# RP2040LED.net
KiCad netlist of a schematic drawn in Altium Designer
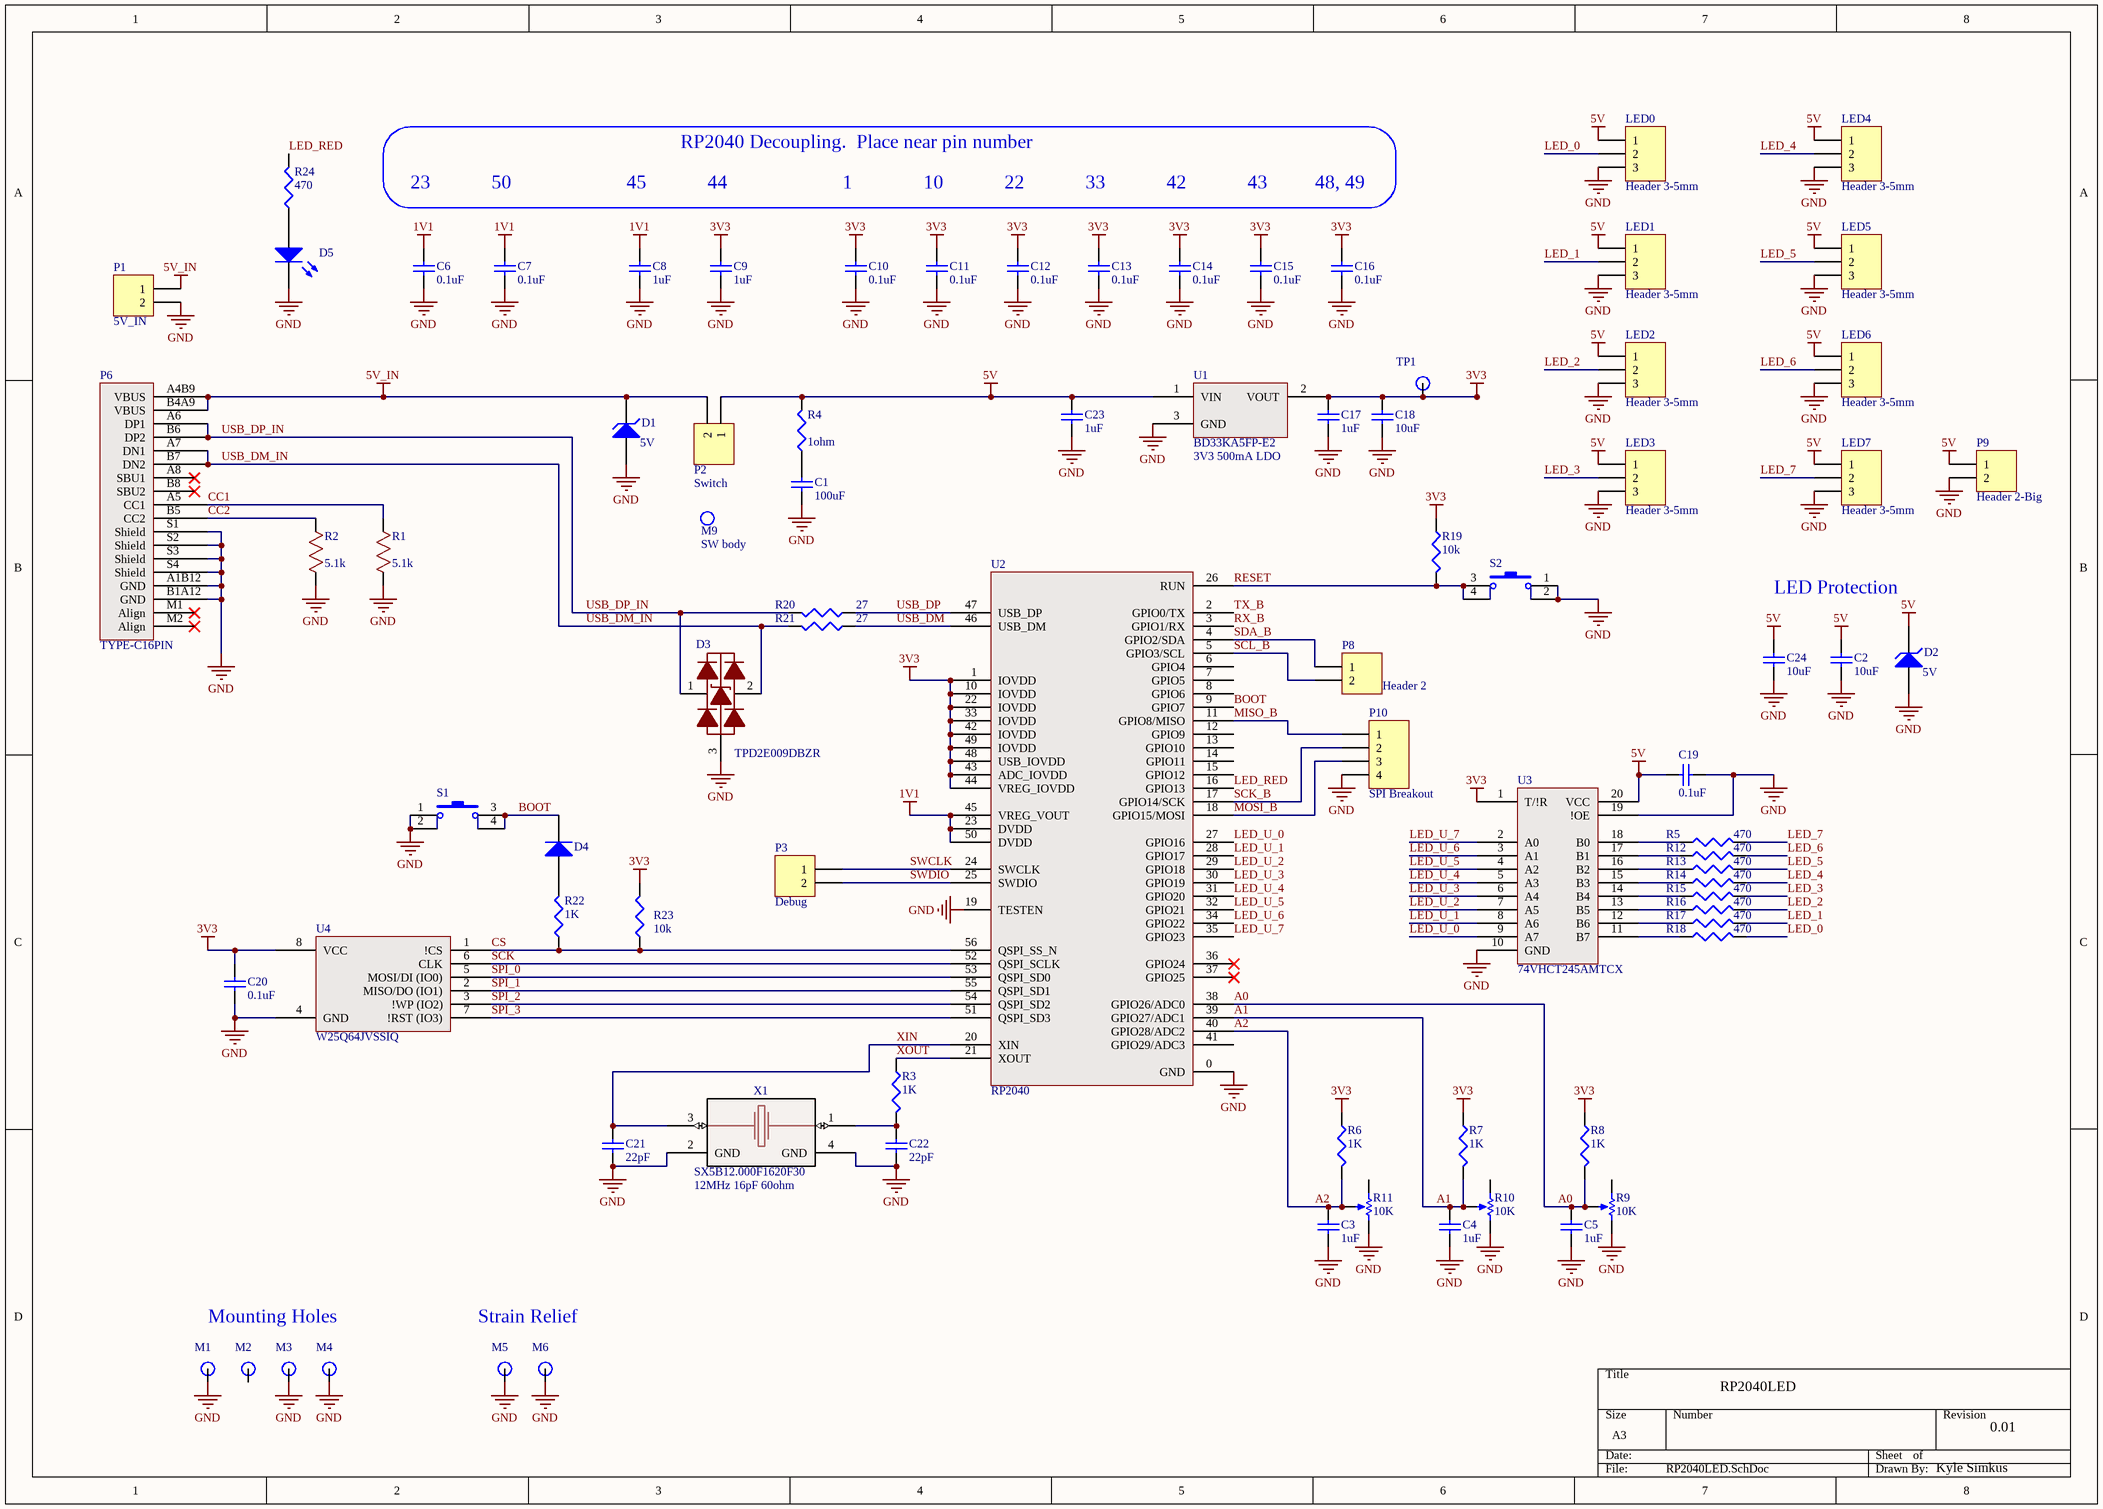
[diagram p0: RP2040LED.SchDoc]

(export (version "E")
  (design (tool "Eeschema 10.0.6"))
  (components
    (comp (ref "C1")
      (value "100uF")
      (footprint "1210 [3225] - C")
      (description "10V 100uF X5R ±20% 1210  Multilayer Ceramic Capacitors MLCC - SMD/SMT ROHS")
      (fields (field (name "VOLTAGE") "10V") (field (name "Comment") "CAP"))
      (libsource (lib "Miscellaneous Devices") (part "Cap Semi"))
    )
    (comp (ref "C2")
      (value "10uF")
      (footprint "0805 [2012] - C")
      (description "MULTILAYER CERAMIC CAPACITORS MLCC - SMD/SMT 10UF 25V 0805 ROHS")
      (fields (field (name "VOLTAGE") "V") (field (name "MPN") "CL21A106KOQNNNE"))
      (libsource (lib "Miscellaneous Devices") (part "Cap Semi"))
    )
    (comp (ref "C3")
      (value "1uF")
      (footprint "0603C")
      (description "MULTILAYER CERAMIC CAPACITORS MLCC - SMD/SMT 1UF 50V 0603 ROHS")
      (fields (field (name "VOLTAGE") "V") (field (name "MPN") "CL10A105KA8NNNC"))
      (libsource (lib "Miscellaneous Devices") (part "Cap Semi"))
    )
    (comp (ref "C4")
      (value "1uF")
      (footprint "0603C")
      (description "MULTILAYER CERAMIC CAPACITORS MLCC - SMD/SMT 1UF 50V 0603 ROHS")
      (fields (field (name "VOLTAGE") "V") (field (name "MPN") "CL10A105KA8NNNC"))
      (libsource (lib "Miscellaneous Devices") (part "Cap Semi"))
    )
    (comp (ref "C5")
      (value "1uF")
      (footprint "0603C")
      (description "MULTILAYER CERAMIC CAPACITORS MLCC - SMD/SMT 1UF 50V 0603 ROHS")
      (fields (field (name "VOLTAGE") "V") (field (name "MPN") "CL10A105KA8NNNC"))
      (libsource (lib "Miscellaneous Devices") (part "Cap Semi"))
    )
    (comp (ref "C6")
      (value "0.1uF")
      (footprint "0402C")
      (description "MULTILAYER CERAMIC CAPACITORS MLCC - SMD/SMT 100NF 50V 0603 ROHS")
      (fields (field (name "VOLTAGE") "V") (field (name "MPN") "CL05B104KB54PNC"))
      (libsource (lib "Miscellaneous Devices") (part "Cap Semi"))
    )
    (comp (ref "C7")
      (value "0.1uF")
      (footprint "0402C")
      (description "MULTILAYER CERAMIC CAPACITORS MLCC - SMD/SMT 100NF 50V 0603 ROHS")
      (fields (field (name "VOLTAGE") "V") (field (name "MPN") "CL05B104KB54PNC"))
      (libsource (lib "Miscellaneous Devices") (part "Cap Semi"))
    )
    (comp (ref "C8")
      (value "1uF")
      (footprint "0603C")
      (description "MULTILAYER CERAMIC CAPACITORS MLCC - SMD/SMT 1UF 50V 0603 ROHS")
      (fields (field (name "VOLTAGE") "V") (field (name "MPN") "CL10A105KA8NNNC"))
      (libsource (lib "Miscellaneous Devices") (part "Cap Semi"))
    )
    (comp (ref "C9")
      (value "1uF")
      (footprint "0603C")
      (description "MULTILAYER CERAMIC CAPACITORS MLCC - SMD/SMT 1UF 50V 0603 ROHS")
      (fields (field (name "VOLTAGE") "V") (field (name "MPN") "CL10A105KA8NNNC"))
      (libsource (lib "Miscellaneous Devices") (part "Cap Semi"))
    )
    (comp (ref "C10")
      (value "0.1uF")
      (footprint "0402C")
      (description "MULTILAYER CERAMIC CAPACITORS MLCC - SMD/SMT 100NF 50V 0603 ROHS")
      (fields (field (name "VOLTAGE") "V") (field (name "MPN") "CL05B104KB54PNC"))
      (libsource (lib "Miscellaneous Devices") (part "Cap Semi"))
    )
    (comp (ref "C11")
      (value "0.1uF")
      (footprint "0402C")
      (description "MULTILAYER CERAMIC CAPACITORS MLCC - SMD/SMT 100NF 50V 0603 ROHS")
      (fields (field (name "VOLTAGE") "V") (field (name "MPN") "CL05B104KB54PNC"))
      (libsource (lib "Miscellaneous Devices") (part "Cap Semi"))
    )
    (comp (ref "C12")
      (value "0.1uF")
      (footprint "0402C")
      (description "MULTILAYER CERAMIC CAPACITORS MLCC - SMD/SMT 100NF 50V 0603 ROHS")
      (fields (field (name "VOLTAGE") "V") (field (name "MPN") "CL05B104KB54PNC"))
      (libsource (lib "Miscellaneous Devices") (part "Cap Semi"))
    )
    (comp (ref "C13")
      (value "0.1uF")
      (footprint "0402C")
      (description "MULTILAYER CERAMIC CAPACITORS MLCC - SMD/SMT 100NF 50V 0603 ROHS")
      (fields (field (name "VOLTAGE") "V") (field (name "MPN") "CL05B104KB54PNC"))
      (libsource (lib "Miscellaneous Devices") (part "Cap Semi"))
    )
    (comp (ref "C14")
      (value "0.1uF")
      (footprint "0402C")
      (description "MULTILAYER CERAMIC CAPACITORS MLCC - SMD/SMT 100NF 50V 0603 ROHS")
      (fields (field (name "VOLTAGE") "V") (field (name "MPN") "CL05B104KB54PNC"))
      (libsource (lib "Miscellaneous Devices") (part "Cap Semi"))
    )
    (comp (ref "C15")
      (value "0.1uF")
      (footprint "0402C")
      (description "MULTILAYER CERAMIC CAPACITORS MLCC - SMD/SMT 100NF 50V 0603 ROHS")
      (fields (field (name "VOLTAGE") "V") (field (name "MPN") "CL05B104KB54PNC"))
      (libsource (lib "Miscellaneous Devices") (part "Cap Semi"))
    )
    (comp (ref "C16")
      (value "0.1uF")
      (footprint "0402C")
      (description "MULTILAYER CERAMIC CAPACITORS MLCC - SMD/SMT 100NF 50V 0603 ROHS")
      (fields (field (name "VOLTAGE") "V") (field (name "MPN") "CL05B104KB54PNC"))
      (libsource (lib "Miscellaneous Devices") (part "Cap Semi"))
    )
    (comp (ref "C17")
      (value "1uF")
      (footprint "0603C")
      (description "MULTILAYER CERAMIC CAPACITORS MLCC - SMD/SMT 1UF 50V 0603 ROHS")
      (fields (field (name "VOLTAGE") "V") (field (name "MPN") "CL10A105KA8NNNC"))
      (libsource (lib "Miscellaneous Devices") (part "Cap Semi"))
    )
    (comp (ref "C18")
      (value "10uF")
      (footprint "0805 [2012] - C")
      (description "MULTILAYER CERAMIC CAPACITORS MLCC - SMD/SMT 10UF 25V 0805 ROHS")
      (fields (field (name "VOLTAGE") "V") (field (name "MPN") "CL21A106KOQNNNE"))
      (libsource (lib "Miscellaneous Devices") (part "Cap Semi"))
    )
    (comp (ref "C19")
      (value "0.1uF")
      (footprint "0603C")
      (description "MULTILAYER CERAMIC CAPACITORS MLCC - SMD/SMT 100NF 50V 0603 ROHS")
      (fields (field (name "VOLTAGE") "V") (field (name "MPN") "CL10B104KB8NNNC"))
      (libsource (lib "Miscellaneous Devices") (part "Cap Semi"))
    )
    (comp (ref "C20")
      (value "0.1uF")
      (footprint "0603C")
      (description "MULTILAYER CERAMIC CAPACITORS MLCC - SMD/SMT 100NF 50V 0603 ROHS")
      (fields (field (name "VOLTAGE") "V") (field (name "MPN") "CL10B104KB8NNNC"))
      (libsource (lib "Miscellaneous Devices") (part "Cap Semi"))
    )
    (comp (ref "C21")
      (value "22pF")
      (footprint "0603C")
      (description "50V 22pF C0G ±5% 0603  Multilayer Ceramic Capacitors MLCC - SMD/SMT ROHS")
      (fields (field (name "VOLTAGE") "50V") (field (name "MPN") "CL10C220JB8NNNC"))
      (libsource (lib "Miscellaneous Devices") (part "Cap Semi"))
    )
    (comp (ref "C22")
      (value "22pF")
      (footprint "0603C")
      (description "50V 22pF C0G ±5% 0603  Multilayer Ceramic Capacitors MLCC - SMD/SMT ROHS")
      (fields (field (name "VOLTAGE") "50V") (field (name "MPN") "CL10C220JB8NNNC"))
      (libsource (lib "Miscellaneous Devices") (part "Cap Semi"))
    )
    (comp (ref "C23")
      (value "1uF")
      (footprint "0603C")
      (description "MULTILAYER CERAMIC CAPACITORS MLCC - SMD/SMT 1UF 50V 0603 ROHS")
      (fields (field (name "VOLTAGE") "V") (field (name "MPN") "CL10A105KA8NNNC"))
      (libsource (lib "Miscellaneous Devices") (part "Cap Semi"))
    )
    (comp (ref "C24")
      (value "10uF")
      (footprint "0805 [2012] - C")
      (description "MULTILAYER CERAMIC CAPACITORS MLCC - SMD/SMT 10UF 25V 0805 ROHS")
      (fields (field (name "VOLTAGE") "V") (field (name "MPN") "CL21A106KOQNNNE"))
      (libsource (lib "Miscellaneous Devices") (part "Cap Semi"))
    )
    (comp (ref "D1")
      (value "5V")
      (footprint "SMA DO-214AC")
      (description "TVS DIODE 5VWM 9.2VC DO214AC")
      (fields (field (name "MANUFACTURER") "Vishay") (field (name "MPN") "SMAJ5.0A-E3/61"))
      (libsource (lib "Miscellaneous Devices") (part "D Zener"))
    )
    (comp (ref "D2")
      (value "5V")
      (footprint "SMA DO-214AC")
      (description "TVS DIODE 5VWM 9.2VC DO214AC")
      (fields (field (name "MANUFACTURER") "Vishay") (field (name "MPN") "SMAJ5.0A-E3/61"))
      (libsource (lib "Miscellaneous Devices") (part "D Zener"))
    )
    (comp (ref "D3")
      (value "D_TVS-BI2C_SOT23")
      (footprint "SOT23-3-TPD2E009DBZR")
      (description "IC ESD-Protection ARRAY Dual High Speed SOT23-3")
      (fields (field (name "DK MPN") "TPD2E009DBZR") (field (name "MPN") "TPD2E009DBZR"))
      (libsource (lib "UnifiedLibraryDBlib") (part "D_TVS-BI2C_SOT23"))
    )
    (comp (ref "D4")
      (value "~")
      (footprint "DO-214AC-C95872")
      (description "1A 1kV 1.1V@1A SMA(DO-214AC) Diodes - General Purpose")
      (libsource (lib "Miscellaneous Devices") (part "Diode"))
    )
    (comp (ref "D5")
      (value "~")
      (footprint "0603LED-KT-0603R")
      (description "LED red 0603 20mA 2V")
      (libsource (lib "Miscellaneous Devices") (part "LED1"))
    )
    (comp (ref "LED0")
      (value "Header 3-5mm")
      (footprint "Header3-5mm")
      (description "Header, 3-Pin")
      (libsource (lib "Miscellaneous Connectors") (part "Header 3"))
    )
    (comp (ref "LED1")
      (value "Header 3-5mm")
      (footprint "Header3-5mm")
      (description "Header, 3-Pin")
      (libsource (lib "Miscellaneous Connectors") (part "Header 3"))
    )
    (comp (ref "LED2")
      (value "Header 3-5mm")
      (footprint "Header3-5mm")
      (description "Header, 3-Pin")
      (libsource (lib "Miscellaneous Connectors") (part "Header 3"))
    )
    (comp (ref "LED3")
      (value "Header 3-5mm")
      (footprint "Header3-5mm")
      (description "Header, 3-Pin")
      (libsource (lib "Miscellaneous Connectors") (part "Header 3"))
    )
    (comp (ref "LED4")
      (value "Header 3-5mm")
      (footprint "Header3-5mm")
      (description "Header, 3-Pin")
      (libsource (lib "Miscellaneous Connectors") (part "Header 3"))
    )
    (comp (ref "LED5")
      (value "Header 3-5mm")
      (footprint "Header3-5mm")
      (description "Header, 3-Pin")
      (libsource (lib "Miscellaneous Connectors") (part "Header 3"))
    )
    (comp (ref "LED6")
      (value "Header 3-5mm")
      (footprint "Header3-5mm")
      (description "Header, 3-Pin")
      (libsource (lib "Miscellaneous Connectors") (part "Header 3"))
    )
    (comp (ref "LED7")
      (value "Header 3-5mm")
      (footprint "Header3-5mm")
      (description "Header, 3-Pin")
      (libsource (lib "Miscellaneous Connectors") (part "Header 3"))
    )
    (comp (ref "M1")
      (value "Mounting hole")
      (footprint "MOUNT_3mm_5mm")
      (libsource (lib "peta") (part "TestPoint"))
    )
    (comp (ref "M2")
      (value "Mounting hole")
      (footprint "MOUNT_3mm_5mm")
      (libsource (lib "peta") (part "TestPoint"))
    )
    (comp (ref "M3")
      (value "Mounting hole")
      (footprint "MOUNT_3mm_5mm")
      (libsource (lib "peta") (part "TestPoint"))
    )
    (comp (ref "M4")
      (value "Mounting hole")
      (footprint "MOUNT_3mm_5mm")
      (libsource (lib "peta") (part "TestPoint"))
    )
    (comp (ref "M5")
      (value "Mounting hole")
      (footprint "MOUNT_3mm_5mm")
      (libsource (lib "peta") (part "TestPoint"))
    )
    (comp (ref "M6")
      (value "Mounting hole")
      (footprint "MOUNT_3mm_5mm")
      (libsource (lib "peta") (part "TestPoint"))
    )
    (comp (ref "M9")
      (value "no pins")
      (footprint "Rocker Switch - BODY")
      (fields (field (name "ALTIUM_UNNAMED_1") "SW body"))
      (libsource (lib "RP2040LED") (part "Mech"))
    )
    (comp (ref "P1")
      (value "5V_IN")
      (footprint "Header2-BIG")
      (description "Header, 2-Pin")
      (libsource (lib "Miscellaneous Connectors") (part "Header 2"))
    )
    (comp (ref "P2")
      (value "Switch")
      (footprint "Header2-BIG")
      (description "Header, 2-Pin")
      (libsource (lib "Miscellaneous Connectors") (part "Header 2"))
    )
    (comp (ref "P3")
      (value "Debug")
      (footprint "HDR1X2")
      (description "Header, 2-Pin")
      (fields (field (name "PUBLISHER") "Altium Limited"))
      (libsource (lib "Miscellaneous Connectors") (part "Header 2"))
    )
    (comp (ref "P6")
      (value "USB-C")
      (footprint "USB-TYPE-C16PIN")
      (description "3A 1 Surface Mount 16P Female -40℃~+85℃ Type-C SMD  USB Connectors ROHS")
      (fields (field (name "JLC MPN") "TYPE-C16PIN"))
      (libsource (lib "RP2040LED") (part "USB-C"))
    )
    (comp (ref "P8")
      (value "Header 2")
      (footprint "HDR1X2")
      (description "Header, 2-Pin")
      (libsource (lib "") (part "Header 2_1"))
    )
    (comp (ref "P9")
      (value "Header 2-Big")
      (footprint "Header2-BIG")
      (description "Header, 2-Pin")
      (libsource (lib "") (part "Header 2_1"))
    )
    (comp (ref "P10")
      (value "SPI Breakout")
      (footprint "HDR1X4")
      (description "Header, 4-Pin")
      (fields (field (name "PUBLISHER") "Altium Limited"))
      (libsource (lib "Miscellaneous Connectors") (part "Header 4"))
    )
    (comp (ref "R1")
      (value "5.1k")
      (footprint "0603R")
      (description "CHIP RESISTOR - SURFACE MOUNT 5.1KOHMS ±1% 1/10W 0603 ROHS")
      (fields (field (name "Comment") "R_RES_0603"))
      (libsource (lib "UnifiedLibraryDBlib") (part "R_RES_0402"))
    )
    (comp (ref "R2")
      (value "5.1k")
      (footprint "0603R")
      (description "CHIP RESISTOR - SURFACE MOUNT 5.1KOHMS ±1% 1/10W 0603 ROHS")
      (fields (field (name "Comment") "R_RES_0603"))
      (libsource (lib "UnifiedLibraryDBlib") (part "R_RES_0402"))
    )
    (comp (ref "R3")
      (value "1K")
      (footprint "0603R")
      (description "100mW Thick Film Resistors ±5% ±200ppm/℃ 1000ohm 0603  Chip Resistor - Surface Mount ROHS")
      (fields (field (name "Comment") "Res3"))
      (libsource (lib "Miscellaneous Devices") (part "Res3"))
    )
    (comp (ref "R4")
      (value "1ohm")
      (footprint "0805R")
      (description "RES 1 OHM 5% 1/2W 0805")
      (fields (field (name "Comment") "Res3"))
      (libsource (lib "Miscellaneous Devices") (part "Res3"))
    )
    (comp (ref "R5")
      (value "470")
      (footprint "0603R")
      (description "CHIP RESISTOR - SURFACE MOUNT 470OHMS ±1% 1/10W 0603 ROHS")
      (fields (field (name "MPN") "ERJ-3EKF4700V"))
      (libsource (lib "Miscellaneous Devices") (part "Res3"))
    )
    (comp (ref "R6")
      (value "1K")
      (footprint "0603R")
      (description "100mW Thick Film Resistors ±5% ±200ppm/℃ 1000ohm 0603  Chip Resistor - Surface Mount ROHS")
      (fields (field (name "Comment") "Res3"))
      (libsource (lib "Miscellaneous Devices") (part "Res3"))
    )
    (comp (ref "R7")
      (value "1K")
      (footprint "0603R")
      (description "100mW Thick Film Resistors ±5% ±200ppm/℃ 1000ohm 0603  Chip Resistor - Surface Mount ROHS")
      (fields (field (name "Comment") "Res3"))
      (libsource (lib "Miscellaneous Devices") (part "Res3"))
    )
    (comp (ref "R8")
      (value "1K")
      (footprint "0603R")
      (description "100mW Thick Film Resistors ±5% ±200ppm/℃ 1000ohm 0603  Chip Resistor - Surface Mount ROHS")
      (fields (field (name "Comment") "Res3"))
      (libsource (lib "Miscellaneous Devices") (part "Res3"))
    )
    (comp (ref "R9")
      (value "10K")
      (footprint "TrimPot-ext-Knob")
      (description "Potentiometer")
      (fields (field (name "MFG") "WMYCONGCONG") (field (name "Comment") "RPot"))
      (libsource (lib "Miscellaneous Devices") (part "RPot"))
    )
    (comp (ref "R10")
      (value "10K")
      (footprint "TrimPot-ext-Knob")
      (description "Potentiometer")
      (fields (field (name "MFG") "WMYCONGCONG") (field (name "Comment") "RPot"))
      (libsource (lib "Miscellaneous Devices") (part "RPot"))
    )
    (comp (ref "R11")
      (value "10K")
      (footprint "TrimPot-ext-Knob")
      (description "Potentiometer")
      (fields (field (name "MFG") "WMYCONGCONG") (field (name "Comment") "RPot"))
      (libsource (lib "Miscellaneous Devices") (part "RPot"))
    )
    (comp (ref "R12")
      (value "470")
      (footprint "0603R")
      (description "CHIP RESISTOR - SURFACE MOUNT 470OHMS ±1% 1/10W 0603 ROHS")
      (fields (field (name "MPN") "ERJ-3EKF4700V"))
      (libsource (lib "Miscellaneous Devices") (part "Res3"))
    )
    (comp (ref "R13")
      (value "470")
      (footprint "0603R")
      (description "CHIP RESISTOR - SURFACE MOUNT 470OHMS ±1% 1/10W 0603 ROHS")
      (fields (field (name "MPN") "ERJ-3EKF4700V"))
      (libsource (lib "Miscellaneous Devices") (part "Res3"))
    )
    (comp (ref "R14")
      (value "470")
      (footprint "0603R")
      (description "CHIP RESISTOR - SURFACE MOUNT 470OHMS ±1% 1/10W 0603 ROHS")
      (fields (field (name "MPN") "ERJ-3EKF4700V"))
      (libsource (lib "Miscellaneous Devices") (part "Res3"))
    )
    (comp (ref "R15")
      (value "470")
      (footprint "0603R")
      (description "CHIP RESISTOR - SURFACE MOUNT 470OHMS ±1% 1/10W 0603 ROHS")
      (fields (field (name "MPN") "ERJ-3EKF4700V"))
      (libsource (lib "Miscellaneous Devices") (part "Res3"))
    )
    (comp (ref "R16")
      (value "470")
      (footprint "0603R")
      (description "CHIP RESISTOR - SURFACE MOUNT 470OHMS ±1% 1/10W 0603 ROHS")
      (fields (field (name "MPN") "ERJ-3EKF4700V"))
      (libsource (lib "Miscellaneous Devices") (part "Res3"))
    )
    (comp (ref "R17")
      (value "470")
      (footprint "0603R")
      (description "CHIP RESISTOR - SURFACE MOUNT 470OHMS ±1% 1/10W 0603 ROHS")
      (fields (field (name "MPN") "ERJ-3EKF4700V"))
      (libsource (lib "Miscellaneous Devices") (part "Res3"))
    )
    (comp (ref "R18")
      (value "470")
      (footprint "0603R")
      (description "CHIP RESISTOR - SURFACE MOUNT 470OHMS ±1% 1/10W 0603 ROHS")
      (fields (field (name "MPN") "ERJ-3EKF4700V"))
      (libsource (lib "Miscellaneous Devices") (part "Res3"))
    )
    (comp (ref "R19")
      (value "10k")
      (footprint "0603R")
      (description "CHIP RESISTOR - SURFACE MOUNT 10KOHMS ±1% 1/10W 0603 ROHS")
      (fields (field (name "MPN") "ERJ-3GEYJ103V"))
      (libsource (lib "Miscellaneous Devices") (part "Res3"))
    )
    (comp (ref "R20")
      (value "27")
      (footprint "0603R")
      (description "100mW Thick Film Resistors ±1% ±200ppm/℃ 27ohm 0603 Chip Resistor - Surface Mount ROHS")
      (fields (field (name "MPN") "0603WAF270JT5E"))
      (libsource (lib "Miscellaneous Devices") (part "Res3"))
    )
    (comp (ref "R21")
      (value "27")
      (footprint "0603R")
      (description "100mW Thick Film Resistors ±1% ±200ppm/℃ 27ohm 0603 Chip Resistor - Surface Mount ROHS")
      (fields (field (name "MPN") "0603WAF270JT5E"))
      (libsource (lib "Miscellaneous Devices") (part "Res3"))
    )
    (comp (ref "R22")
      (value "1K")
      (footprint "0603R")
      (description "100mW Thick Film Resistors ±5% ±200ppm/℃ 1000ohm 0603  Chip Resistor - Surface Mount ROHS")
      (fields (field (name "Comment") "Res3"))
      (libsource (lib "Miscellaneous Devices") (part "Res3"))
    )
    (comp (ref "R23")
      (value "10k")
      (footprint "0603R")
      (description "CHIP RESISTOR - SURFACE MOUNT 10KOHMS ±1% 1/10W 0603 ROHS")
      (fields (field (name "MPN") "ERJ-3GEYJ103V"))
      (libsource (lib "Miscellaneous Devices") (part "Res3"))
    )
    (comp (ref "R24")
      (value "470")
      (footprint "0603R")
      (description "CHIP RESISTOR - SURFACE MOUNT 470OHMS ±1% 1/10W 0603 ROHS")
      (fields (field (name "MPN") "ERJ-3EKF4700V") (field (name "Comment") "470ohm"))
      (libsource (lib "Miscellaneous Devices") (part "Res3"))
    )
    (comp (ref "S1")
      (value "SW-PB")
      (footprint "SW_KMR211GLFS")
      (description "0.05A Brick nogging SPST - NO 120gf 32V SMD  Tactile Switches ROHS")
      (libsource (lib "shim") (part "SW-PB"))
    )
    (comp (ref "S2")
      (value "SW-PB")
      (footprint "SW_KMR211GLFS")
      (description "0.05A Brick nogging SPST - NO 120gf 32V SMD  Tactile Switches ROHS")
      (libsource (lib "shim") (part "SW-PB"))
    )
    (comp (ref "TP1")
      (value "3V3")
      (footprint "TestPoint 0.9mm 2mm")
      (description "Test Point")
      (libsource (lib "peta") (part "TestPoint"))
    )
    (comp (ref "U1")
      (value "LDO-BD33KA5FP-E2")
      (footprint "TO-252-3-BD33KA5FP-E2")
      (description "500mA 50dB@(120Hz) Fixed 3.3V Positive 5.5V TO-252")
      (fields
        (field (name "VOLTAGE") "3.3V")
        (field (name "JLC MPN") "BD33KA5FP-E2")
        (field (name "NOTE") "3V3 500mA LDO")
      )
      (libsource (lib "RP2040LED") (part "LDO-BD33KA5FP-E2"))
    )
    (comp (ref "U2")
      (value "RP2040")
      (footprint "56-QFN-RP2040")
      (description "RPi RP2040 133MHz 32bit dual core 30 I/O 264K x8 4x12bit ADC")
      (fields (field (name "JLC MPN") "RP2040"))
      (libsource (lib "RP2040LED") (part "RP2040"))
    )
    (comp (ref "U3")
      (value "74VHCT245AMTCX")
      (footprint "20-TSSOP-74VHCT245AMTCX")
      (description "8 8mA 4.5V~5.5V 8mA 1 TSSOP-20  Buffer/Driver/Transceiver ROHS")
      (fields (field (name "MFG") "onsemi") (field (name "JLC MPN") "74VHCT245AMTCX"))
      (libsource (lib "RP2040LED") (part "74VHCT245AMTCX"))
    )
    (comp (ref "U4")
      (value "FLASH")
      (footprint "8-SOIC-W25Q64JVSSIQ")
      (description "SOP-8-208mil  NOR FLASH ROHS")
      (fields (field (name "JLC MPN") "W25Q64JVSSIQ"))
      (libsource (lib "RP2040LED") (part "W25Q64JVSSIQ"))
    )
    (comp (ref "X1")
      (value "12MHz 16pF 60ohm")
      (footprint "4-SMD-XTAL-C2901628")
      (description "12MHz 16pF ±20ppm SMD5032-4P 60ohm")
      (fields
        (field (name "MFG") "Shenzhen SCTF Elec")
        (field (name "JLC MPN") "SX5B12.000F1620F30")
        (field (name "Comment") "X_XTAL_4SMD")
      )
      (libsource (lib "HP") (part "X_XTAL_4"))
    )
  )
  (nets
    (net (code "1") (name "/A0") (class "Default")
      (node (ref "C5") (pin "1") (pinfunction "1_1") (pintype "passive"))
      (node (ref "R8") (pin "1") (pinfunction "1_1") (pintype "passive"))
      (node (ref "R9") (pin "3") (pinfunction "TAP_3") (pintype "passive"))
      (node (ref "U2") (pin "38") (pinfunction "GPIO26/ADC0_38") (pintype "passive"))
    )
    (net (code "2") (name "/A1") (class "Default")
      (node (ref "C4") (pin "1") (pinfunction "1_1") (pintype "passive"))
      (node (ref "R10") (pin "3") (pinfunction "TAP_3") (pintype "passive"))
      (node (ref "R7") (pin "1") (pinfunction "1_1") (pintype "passive"))
      (node (ref "U2") (pin "39") (pinfunction "GPIO27/ADC1_39") (pintype "passive"))
    )
    (net (code "3") (name "/A2") (class "Default")
      (node (ref "C3") (pin "1") (pinfunction "1_1") (pintype "passive"))
      (node (ref "R11") (pin "3") (pinfunction "TAP_3") (pintype "passive"))
      (node (ref "R6") (pin "1") (pinfunction "1_1") (pintype "passive"))
      (node (ref "U2") (pin "40") (pinfunction "GPIO28/ADC2_40") (pintype "passive"))
    )
    (net (code "4") (name "/BOOT") (class "Default")
      (node (ref "D4") (pin "2") (pinfunction "K_2") (pintype "passive"))
      (node (ref "S1") (pin "3") (pinfunction "3_3") (pintype "passive"))
      (node (ref "S1") (pin "4") (pinfunction "4_4") (pintype "passive"))
      (node (ref "U2") (pin "9") (pinfunction "GPIO7_9") (pintype "passive"))
    )
    (net (code "5") (name "/CC1") (class "Default")
      (node (ref "P6") (pin "A5") (pinfunction "CC1_A5") (pintype "passive"))
      (node (ref "R1") (pin "1") (pinfunction "1_1") (pintype "passive"))
    )
    (net (code "6") (name "/CC2") (class "Default")
      (node (ref "P6") (pin "B5") (pinfunction "CC2_B5") (pintype "passive"))
      (node (ref "R2") (pin "1") (pinfunction "1_1") (pintype "passive"))
    )
    (net (code "7") (name "/CS") (class "Default")
      (node (ref "R22") (pin "1") (pinfunction "1_1") (pintype "passive"))
      (node (ref "R23") (pin "1") (pinfunction "1_1") (pintype "passive"))
      (node (ref "U2") (pin "56") (pinfunction "QSPI_SS_N_56") (pintype "passive"))
      (node (ref "U4") (pin "1") (pinfunction "!CS_1") (pintype "passive"))
    )
    (net (code "8") (name "/LED_0") (class "Default")
      (node (ref "LED0") (pin "2") (pinfunction "2_2") (pintype "passive"))
      (node (ref "R18") (pin "2") (pinfunction "2_2") (pintype "passive"))
    )
    (net (code "9") (name "/LED_1") (class "Default")
      (node (ref "LED1") (pin "2") (pinfunction "2_2") (pintype "passive"))
      (node (ref "R17") (pin "2") (pinfunction "2_2") (pintype "passive"))
    )
    (net (code "10") (name "/LED_2") (class "Default")
      (node (ref "LED2") (pin "2") (pinfunction "2_2") (pintype "passive"))
      (node (ref "R16") (pin "2") (pinfunction "2_2") (pintype "passive"))
    )
    (net (code "11") (name "/LED_3") (class "Default")
      (node (ref "LED3") (pin "2") (pinfunction "2_2") (pintype "passive"))
      (node (ref "R15") (pin "2") (pinfunction "2_2") (pintype "passive"))
    )
    (net (code "12") (name "/LED_4") (class "Default")
      (node (ref "LED4") (pin "2") (pinfunction "2_2") (pintype "passive"))
      (node (ref "R14") (pin "2") (pinfunction "2_2") (pintype "passive"))
    )
    (net (code "13") (name "/LED_5") (class "Default")
      (node (ref "LED5") (pin "2") (pinfunction "2_2") (pintype "passive"))
      (node (ref "R13") (pin "2") (pinfunction "2_2") (pintype "passive"))
    )
    (net (code "14") (name "/LED_6") (class "Default")
      (node (ref "LED6") (pin "2") (pinfunction "2_2") (pintype "passive"))
      (node (ref "R12") (pin "2") (pinfunction "2_2") (pintype "passive"))
    )
    (net (code "15") (name "/LED_7") (class "Default")
      (node (ref "LED7") (pin "2") (pinfunction "2_2") (pintype "passive"))
      (node (ref "R5") (pin "2") (pinfunction "2_2") (pintype "passive"))
    )
    (net (code "16") (name "/LED_RED") (class "Default")
      (node (ref "R24") (pin "2") (pinfunction "2_2") (pintype "passive"))
      (node (ref "U2") (pin "16") (pinfunction "GPIO13_16") (pintype "passive"))
    )
    (net (code "17") (name "/LED_U_0") (class "Default")
      (node (ref "U2") (pin "27") (pinfunction "GPIO16_27") (pintype "passive"))
      (node (ref "U3") (pin "9") (pinfunction "A7_9") (pintype "passive"))
    )
    (net (code "18") (name "/LED_U_1") (class "Default")
      (node (ref "U2") (pin "28") (pinfunction "GPIO17_28") (pintype "passive"))
      (node (ref "U3") (pin "8") (pinfunction "A6_8") (pintype "passive"))
    )
    (net (code "19") (name "/LED_U_2") (class "Default")
      (node (ref "U2") (pin "29") (pinfunction "GPIO18_29") (pintype "passive"))
      (node (ref "U3") (pin "7") (pinfunction "A5_7") (pintype "passive"))
    )
    (net (code "20") (name "/LED_U_3") (class "Default")
      (node (ref "U2") (pin "30") (pinfunction "GPIO19_30") (pintype "passive"))
      (node (ref "U3") (pin "6") (pinfunction "A4_6") (pintype "passive"))
    )
    (net (code "21") (name "/LED_U_4") (class "Default")
      (node (ref "U2") (pin "31") (pinfunction "GPIO20_31") (pintype "passive"))
      (node (ref "U3") (pin "5") (pinfunction "A3_5") (pintype "passive"))
    )
    (net (code "22") (name "/LED_U_5") (class "Default")
      (node (ref "U2") (pin "32") (pinfunction "GPIO21_32") (pintype "passive"))
      (node (ref "U3") (pin "4") (pinfunction "A2_4") (pintype "passive"))
    )
    (net (code "23") (name "/LED_U_6") (class "Default")
      (node (ref "U2") (pin "34") (pinfunction "GPIO22_34") (pintype "passive"))
      (node (ref "U3") (pin "3") (pinfunction "A1_3") (pintype "passive"))
    )
    (net (code "24") (name "/LED_U_7") (class "Default")
      (node (ref "U2") (pin "35") (pinfunction "GPIO23_35") (pintype "passive"))
      (node (ref "U3") (pin "2") (pinfunction "A0_2") (pintype "passive"))
    )
    (net (code "25") (name "/MISO_B") (class "Default")
      (node (ref "P10") (pin "1") (pinfunction "1_1") (pintype "passive"))
      (node (ref "U2") (pin "11") (pinfunction "GPIO8/MISO_11") (pintype "passive"))
    )
    (net (code "26") (name "/MOSI_B") (class "Default")
      (node (ref "P10") (pin "3") (pinfunction "3_3") (pintype "passive"))
      (node (ref "U2") (pin "18") (pinfunction "GPIO15/MOSI_18") (pintype "passive"))
    )
    (net (code "27") (name "/RESET") (class "Default")
      (node (ref "R19") (pin "2") (pinfunction "2_2") (pintype "passive"))
      (node (ref "S2") (pin "3") (pinfunction "3_3") (pintype "passive"))
      (node (ref "S2") (pin "4") (pinfunction "4_4") (pintype "passive"))
      (node (ref "U2") (pin "26") (pinfunction "RUN_26") (pintype "passive"))
    )
    (net (code "28") (name "/RX_B") (class "Default")
      (node (ref "U2") (pin "3") (pinfunction "GPIO1/RX_3") (pintype "passive"))
    )
    (net (code "29") (name "/SCK") (class "Default")
      (node (ref "U2") (pin "52") (pinfunction "QSPI_SCLK_52") (pintype "passive"))
      (node (ref "U4") (pin "6") (pinfunction "CLK_6") (pintype "passive"))
    )
    (net (code "30") (name "/SCK_B") (class "Default")
      (node (ref "P10") (pin "2") (pinfunction "2_2") (pintype "passive"))
      (node (ref "U2") (pin "17") (pinfunction "GPIO14/SCK_17") (pintype "passive"))
    )
    (net (code "31") (name "/SCL_B") (class "Default")
      (node (ref "P8") (pin "2") (pinfunction "2_2") (pintype "passive"))
      (node (ref "U2") (pin "5") (pinfunction "GPIO3/SCL_5") (pintype "passive"))
    )
    (net (code "32") (name "/SDA_B") (class "Default")
      (node (ref "P8") (pin "1") (pinfunction "1_1") (pintype "passive"))
      (node (ref "U2") (pin "4") (pinfunction "GPIO2/SDA_4") (pintype "passive"))
    )
    (net (code "33") (name "/SPI_0") (class "Default")
      (node (ref "U2") (pin "53") (pinfunction "QSPI_SD0_53") (pintype "passive"))
      (node (ref "U4") (pin "5") (pinfunction "MOSI/DI_(IO0)_5") (pintype "passive"))
    )
    (net (code "34") (name "/SPI_1") (class "Default")
      (node (ref "U2") (pin "55") (pinfunction "QSPI_SD1_55") (pintype "passive"))
      (node (ref "U4") (pin "2") (pinfunction "MISO/DO_(IO1)_2") (pintype "passive"))
    )
    (net (code "35") (name "/SPI_2") (class "Default")
      (node (ref "U2") (pin "54") (pinfunction "QSPI_SD2_54") (pintype "passive"))
      (node (ref "U4") (pin "3") (pinfunction "!WP_(IO2)_3") (pintype "passive"))
    )
    (net (code "36") (name "/SPI_3") (class "Default")
      (node (ref "U2") (pin "51") (pinfunction "QSPI_SD3_51") (pintype "passive"))
      (node (ref "U4") (pin "7") (pinfunction "!RST_(IO3)_7") (pintype "passive"))
    )
    (net (code "37") (name "/SWCLK") (class "Default")
      (node (ref "P3") (pin "1") (pinfunction "1_1") (pintype "passive"))
      (node (ref "U2") (pin "24") (pinfunction "SWCLK_24") (pintype "passive"))
    )
    (net (code "38") (name "/SWDIO") (class "Default")
      (node (ref "P3") (pin "2") (pinfunction "2_2") (pintype "passive"))
      (node (ref "U2") (pin "25") (pinfunction "SWDIO_25") (pintype "passive"))
    )
    (net (code "39") (name "/TX_B") (class "Default")
      (node (ref "U2") (pin "2") (pinfunction "GPIO0/TX_2") (pintype "passive"))
    )
    (net (code "40") (name "/USB_DM") (class "Default")
      (node (ref "R21") (pin "1") (pinfunction "1_1") (pintype "passive"))
      (node (ref "U2") (pin "46") (pinfunction "USB_DM_46") (pintype "passive"))
    )
    (net (code "41") (name "/USB_DM_IN") (class "Default")
      (node (ref "D3") (pin "2") (pinfunction "D-_2") (pintype "passive"))
      (node (ref "P6") (pin "A7") (pinfunction "DN1_A7") (pintype "passive"))
      (node (ref "P6") (pin "B7") (pinfunction "DN2_B7") (pintype "passive"))
      (node (ref "R21") (pin "2") (pinfunction "2_2") (pintype "passive"))
    )
    (net (code "42") (name "/USB_DP") (class "Default")
      (node (ref "R20") (pin "1") (pinfunction "1_1") (pintype "passive"))
      (node (ref "U2") (pin "47") (pinfunction "USB_DP_47") (pintype "passive"))
    )
    (net (code "43") (name "/USB_DP_IN") (class "Default")
      (node (ref "D3") (pin "1") (pinfunction "D+_1") (pintype "passive"))
      (node (ref "P6") (pin "A6") (pinfunction "DP1_A6") (pintype "passive"))
      (node (ref "P6") (pin "B6") (pinfunction "DP2_B6") (pintype "passive"))
      (node (ref "R20") (pin "2") (pinfunction "2_2") (pintype "passive"))
    )
    (net (code "44") (name "/XIN") (class "Default")
      (node (ref "C21") (pin "1") (pinfunction "1_1") (pintype "passive"))
      (node (ref "U2") (pin "20") (pinfunction "XIN_20") (pintype "passive"))
      (node (ref "X1") (pin "3") (pinfunction "X2_3") (pintype "bidirectional"))
    )
    (net (code "45") (name "/XOUT") (class "Default")
      (node (ref "R3") (pin "1") (pinfunction "1_1") (pintype "passive"))
      (node (ref "U2") (pin "21") (pinfunction "XOUT_21") (pintype "passive"))
    )
    (net (code "46") (name "1V1") (class "Default")
      (node (ref "C6") (pin "1") (pinfunction "1_1") (pintype "passive"))
      (node (ref "C7") (pin "1") (pinfunction "1_1") (pintype "passive"))
      (node (ref "C8") (pin "1") (pinfunction "1_1") (pintype "passive"))
      (node (ref "U2") (pin "23") (pinfunction "DVDD_23") (pintype "passive"))
      (node (ref "U2") (pin "45") (pinfunction "VREG_VOUT_45") (pintype "passive"))
      (node (ref "U2") (pin "50") (pinfunction "DVDD_50") (pintype "passive"))
    )
    (net (code "47") (name "3V3") (class "Default")
      (node (ref "C10") (pin "1") (pinfunction "1_1") (pintype "passive"))
      (node (ref "C11") (pin "1") (pinfunction "1_1") (pintype "passive"))
      (node (ref "C12") (pin "1") (pinfunction "1_1") (pintype "passive"))
      (node (ref "C13") (pin "1") (pinfunction "1_1") (pintype "passive"))
      (node (ref "C14") (pin "1") (pinfunction "1_1") (pintype "passive"))
      (node (ref "C15") (pin "1") (pinfunction "1_1") (pintype "passive"))
      (node (ref "C16") (pin "1") (pinfunction "1_1") (pintype "passive"))
      (node (ref "C17") (pin "1") (pinfunction "1_1") (pintype "passive"))
      (node (ref "C18") (pin "2") (pinfunction "2_2") (pintype "passive"))
      (node (ref "C20") (pin "2") (pinfunction "2_2") (pintype "passive"))
      (node (ref "C9") (pin "1") (pinfunction "1_1") (pintype "passive"))
      (node (ref "R19") (pin "1") (pinfunction "1_1") (pintype "passive"))
      (node (ref "R23") (pin "2") (pinfunction "2_2") (pintype "passive"))
      (node (ref "R6") (pin "2") (pinfunction "2_2") (pintype "passive"))
      (node (ref "R7") (pin "2") (pinfunction "2_2") (pintype "passive"))
      (node (ref "R8") (pin "2") (pinfunction "2_2") (pintype "passive"))
      (node (ref "TP1") (pin "1") (pinfunction "TP_1") (pintype "passive"))
      (node (ref "U1") (pin "2") (pinfunction "VOUT_2") (pintype "passive"))
      (node (ref "U2") (pin "1") (pinfunction "IOVDD_1") (pintype "passive"))
      (node (ref "U2") (pin "10") (pinfunction "IOVDD_10") (pintype "passive"))
      (node (ref "U2") (pin "22") (pinfunction "IOVDD_22") (pintype "passive"))
      (node (ref "U2") (pin "33") (pinfunction "IOVDD_33") (pintype "passive"))
      (node (ref "U2") (pin "42") (pinfunction "IOVDD_42") (pintype "passive"))
      (node (ref "U2") (pin "43") (pinfunction "ADC_IOVDD_43") (pintype "passive"))
      (node (ref "U2") (pin "44") (pinfunction "VREG_IOVDD_44") (pintype "passive"))
      (node (ref "U2") (pin "48") (pinfunction "USB_IOVDD_48") (pintype "passive"))
      (node (ref "U2") (pin "49") (pinfunction "IOVDD_49") (pintype "passive"))
      (node (ref "U3") (pin "1") (pinfunction "T/!R_1") (pintype "passive"))
      (node (ref "U4") (pin "8") (pinfunction "VCC_8") (pintype "passive"))
    )
    (net (code "48") (name "5V") (class "Default")
      (node (ref "C19") (pin "1") (pinfunction "1_1") (pintype "passive"))
      (node (ref "C2") (pin "2") (pinfunction "2_2") (pintype "passive"))
      (node (ref "C23") (pin "1") (pinfunction "1_1") (pintype "passive"))
      (node (ref "C24") (pin "2") (pinfunction "2_2") (pintype "passive"))
      (node (ref "D2") (pin "2") (pinfunction "K_2") (pintype "passive"))
      (node (ref "LED0") (pin "1") (pinfunction "1_1") (pintype "passive"))
      (node (ref "LED1") (pin "1") (pinfunction "1_1") (pintype "passive"))
      (node (ref "LED2") (pin "1") (pinfunction "1_1") (pintype "passive"))
      (node (ref "LED3") (pin "1") (pinfunction "1_1") (pintype "passive"))
      (node (ref "LED4") (pin "1") (pinfunction "1_1") (pintype "passive"))
      (node (ref "LED5") (pin "1") (pinfunction "1_1") (pintype "passive"))
      (node (ref "LED6") (pin "1") (pinfunction "1_1") (pintype "passive"))
      (node (ref "LED7") (pin "1") (pinfunction "1_1") (pintype "passive"))
      (node (ref "P2") (pin "1") (pinfunction "1_1") (pintype "passive"))
      (node (ref "P9") (pin "1") (pinfunction "1_1") (pintype "passive"))
      (node (ref "R4") (pin "2") (pinfunction "2_2") (pintype "passive"))
      (node (ref "U1") (pin "1") (pinfunction "VIN_1") (pintype "passive"))
      (node (ref "U3") (pin "20") (pinfunction "VCC_20") (pintype "passive"))
    )
    (net (code "49") (name "5V_IN") (class "Default")
      (node (ref "D1") (pin "2") (pinfunction "K_2") (pintype "passive"))
      (node (ref "P1") (pin "1") (pinfunction "1_1") (pintype "passive"))
      (node (ref "P2") (pin "2") (pinfunction "2_2") (pintype "passive"))
      (node (ref "P6") (pin "A4B9") (pinfunction "VBUS_A4B9") (pintype "passive"))
      (node (ref "P6") (pin "B4A9") (pinfunction "VBUS_B4A9") (pintype "passive"))
    )
    (net (code "50") (name "GND") (class "Default")
      (node (ref "C1") (pin "1") (pinfunction "1_1") (pintype "passive"))
      (node (ref "C10") (pin "2") (pinfunction "2_2") (pintype "passive"))
      (node (ref "C11") (pin "2") (pinfunction "2_2") (pintype "passive"))
      (node (ref "C12") (pin "2") (pinfunction "2_2") (pintype "passive"))
      (node (ref "C13") (pin "2") (pinfunction "2_2") (pintype "passive"))
      (node (ref "C14") (pin "2") (pinfunction "2_2") (pintype "passive"))
      (node (ref "C15") (pin "2") (pinfunction "2_2") (pintype "passive"))
      (node (ref "C16") (pin "2") (pinfunction "2_2") (pintype "passive"))
      (node (ref "C17") (pin "2") (pinfunction "2_2") (pintype "passive"))
      (node (ref "C18") (pin "1") (pinfunction "1_1") (pintype "passive"))
      (node (ref "C19") (pin "2") (pinfunction "2_2") (pintype "passive"))
      (node (ref "C2") (pin "1") (pinfunction "1_1") (pintype "passive"))
      (node (ref "C20") (pin "1") (pinfunction "1_1") (pintype "passive"))
      (node (ref "C21") (pin "2") (pinfunction "2_2") (pintype "passive"))
      (node (ref "C22") (pin "2") (pinfunction "2_2") (pintype "passive"))
      (node (ref "C23") (pin "2") (pinfunction "2_2") (pintype "passive"))
      (node (ref "C24") (pin "1") (pinfunction "1_1") (pintype "passive"))
      (node (ref "C3") (pin "2") (pinfunction "2_2") (pintype "passive"))
      (node (ref "C4") (pin "2") (pinfunction "2_2") (pintype "passive"))
      (node (ref "C5") (pin "2") (pinfunction "2_2") (pintype "passive"))
      (node (ref "C6") (pin "2") (pinfunction "2_2") (pintype "passive"))
      (node (ref "C7") (pin "2") (pinfunction "2_2") (pintype "passive"))
      (node (ref "C8") (pin "2") (pinfunction "2_2") (pintype "passive"))
      (node (ref "C9") (pin "2") (pinfunction "2_2") (pintype "passive"))
      (node (ref "D1") (pin "1") (pinfunction "A_1") (pintype "passive"))
      (node (ref "D2") (pin "1") (pinfunction "A_1") (pintype "passive"))
      (node (ref "D3") (pin "3") (pinfunction "GND_3") (pintype "power_in"))
      (node (ref "D5") (pin "2") (pinfunction "K_2") (pintype "passive"))
      (node (ref "LED0") (pin "3") (pinfunction "3_3") (pintype "passive"))
      (node (ref "LED1") (pin "3") (pinfunction "3_3") (pintype "passive"))
      (node (ref "LED2") (pin "3") (pinfunction "3_3") (pintype "passive"))
      (node (ref "LED3") (pin "3") (pinfunction "3_3") (pintype "passive"))
      (node (ref "LED4") (pin "3") (pinfunction "3_3") (pintype "passive"))
      (node (ref "LED5") (pin "3") (pinfunction "3_3") (pintype "passive"))
      (node (ref "LED6") (pin "3") (pinfunction "3_3") (pintype "passive"))
      (node (ref "LED7") (pin "3") (pinfunction "3_3") (pintype "passive"))
      (node (ref "M1") (pin "1") (pinfunction "TP_1") (pintype "passive"))
      (node (ref "M3") (pin "1") (pinfunction "TP_1") (pintype "passive"))
      (node (ref "M4") (pin "1") (pinfunction "TP_1") (pintype "passive"))
      (node (ref "M5") (pin "1") (pinfunction "TP_1") (pintype "passive"))
      (node (ref "M6") (pin "1") (pinfunction "TP_1") (pintype "passive"))
      (node (ref "P1") (pin "2") (pinfunction "2_2") (pintype "passive"))
      (node (ref "P10") (pin "4") (pinfunction "4_4") (pintype "passive"))
      (node (ref "P6") (pin "A1B12") (pinfunction "GND_A1B12") (pintype "passive"))
      (node (ref "P6") (pin "B1A12") (pinfunction "GND_B1A12") (pintype "passive"))
      (node (ref "P6") (pin "S1") (pinfunction "Shield_S1") (pintype "passive"))
      (node (ref "P6") (pin "S2") (pinfunction "Shield_S2") (pintype "passive"))
      (node (ref "P6") (pin "S3") (pinfunction "Shield_S3") (pintype "passive"))
      (node (ref "P6") (pin "S4") (pinfunction "Shield_S4") (pintype "passive"))
      (node (ref "P9") (pin "2") (pinfunction "2_2") (pintype "passive"))
      (node (ref "R1") (pin "2") (pinfunction "2_2") (pintype "passive"))
      (node (ref "R10") (pin "2") (pinfunction "BOT_2") (pintype "passive"))
      (node (ref "R11") (pin "2") (pinfunction "BOT_2") (pintype "passive"))
      (node (ref "R2") (pin "2") (pinfunction "2_2") (pintype "passive"))
      (node (ref "R9") (pin "2") (pinfunction "BOT_2") (pintype "passive"))
      (node (ref "S1") (pin "1") (pinfunction "1_1") (pintype "passive"))
      (node (ref "S1") (pin "2") (pinfunction "2_2") (pintype "passive"))
      (node (ref "S2") (pin "1") (pinfunction "1_1") (pintype "passive"))
      (node (ref "S2") (pin "2") (pinfunction "2_2") (pintype "passive"))
      (node (ref "U1") (pin "3") (pinfunction "GND_3") (pintype "passive"))
      (node (ref "U2") (pin "0") (pinfunction "GND_0") (pintype "passive"))
      (node (ref "U2") (pin "19") (pinfunction "TESTEN_19") (pintype "passive"))
      (node (ref "U3") (pin "10") (pinfunction "GND_10") (pintype "passive"))
      (node (ref "U3") (pin "19") (pinfunction "!OE_19") (pintype "passive"))
      (node (ref "U4") (pin "4") (pinfunction "GND_4") (pintype "passive"))
      (node (ref "X1") (pin "2") (pinfunction "GND_2") (pintype "power_in"))
      (node (ref "X1") (pin "4") (pinfunction "GND_4") (pintype "power_in"))
    )
    (net (code "51") (name "Net-(C1-Pad2)") (class "Default")
      (node (ref "C1") (pin "2") (pinfunction "2_2") (pintype "passive"))
      (node (ref "R4") (pin "1") (pinfunction "1_1") (pintype "passive"))
    )
    (net (code "52") (name "Net-(D4-A)") (class "Default")
      (node (ref "D4") (pin "1") (pinfunction "A_1") (pintype "passive"))
      (node (ref "R22") (pin "2") (pinfunction "2_2") (pintype "passive"))
    )
    (net (code "53") (name "Net-(D5-A)") (class "Default")
      (node (ref "D5") (pin "1") (pinfunction "A_1") (pintype "passive"))
      (node (ref "R24") (pin "1") (pinfunction "1_1") (pintype "passive"))
    )
    (net (code "54") (name "Net-(U3-B0)") (class "Default")
      (node (ref "R5") (pin "1") (pinfunction "1_1") (pintype "passive"))
      (node (ref "U3") (pin "18") (pinfunction "B0_18") (pintype "passive"))
    )
    (net (code "55") (name "Net-(U3-B1)") (class "Default")
      (node (ref "R12") (pin "1") (pinfunction "1_1") (pintype "passive"))
      (node (ref "U3") (pin "17") (pinfunction "B1_17") (pintype "passive"))
    )
    (net (code "56") (name "Net-(U3-B2)") (class "Default")
      (node (ref "R13") (pin "1") (pinfunction "1_1") (pintype "passive"))
      (node (ref "U3") (pin "16") (pinfunction "B2_16") (pintype "passive"))
    )
    (net (code "57") (name "Net-(U3-B3)") (class "Default")
      (node (ref "R14") (pin "1") (pinfunction "1_1") (pintype "passive"))
      (node (ref "U3") (pin "15") (pinfunction "B3_15") (pintype "passive"))
    )
    (net (code "58") (name "Net-(U3-B4)") (class "Default")
      (node (ref "R15") (pin "1") (pinfunction "1_1") (pintype "passive"))
      (node (ref "U3") (pin "14") (pinfunction "B4_14") (pintype "passive"))
    )
    (net (code "59") (name "Net-(U3-B5)") (class "Default")
      (node (ref "R16") (pin "1") (pinfunction "1_1") (pintype "passive"))
      (node (ref "U3") (pin "13") (pinfunction "B5_13") (pintype "passive"))
    )
    (net (code "60") (name "Net-(U3-B6)") (class "Default")
      (node (ref "R17") (pin "1") (pinfunction "1_1") (pintype "passive"))
      (node (ref "U3") (pin "12") (pinfunction "B6_12") (pintype "passive"))
    )
    (net (code "61") (name "Net-(U3-B7)") (class "Default")
      (node (ref "R18") (pin "1") (pinfunction "1_1") (pintype "passive"))
      (node (ref "U3") (pin "11") (pinfunction "B7_11") (pintype "passive"))
    )
    (net (code "62") (name "Net-(X1-X1)") (class "Default")
      (node (ref "C22") (pin "1") (pinfunction "1_1") (pintype "passive"))
      (node (ref "R3") (pin "2") (pinfunction "2_2") (pintype "passive"))
      (node (ref "X1") (pin "1") (pinfunction "X1_1") (pintype "bidirectional"))
    )
    (net (code "63") (name "unconnected-(M2-TP-Pad1)") (class "Default")
      (node (ref "M2") (pin "1") (pinfunction "TP_1") (pintype "passive"))
    )
    (net (code "64") (name "unconnected-(P6-Align-PadM1)") (class "Default")
      (node (ref "P6") (pin "M1") (pinfunction "Align_M1") (pintype "passive+no_connect"))
    )
    (net (code "65") (name "unconnected-(P6-Align-PadM2)") (class "Default")
      (node (ref "P6") (pin "M2") (pinfunction "Align_M2") (pintype "passive+no_connect"))
    )
    (net (code "66") (name "unconnected-(P6-SBU1-PadA8)") (class "Default")
      (node (ref "P6") (pin "A8") (pinfunction "SBU1_A8") (pintype "passive+no_connect"))
    )
    (net (code "67") (name "unconnected-(P6-SBU2-PadB8)") (class "Default")
      (node (ref "P6") (pin "B8") (pinfunction "SBU2_B8") (pintype "passive+no_connect"))
    )
    (net (code "68") (name "unconnected-(R9-TOP-Pad1)") (class "Default")
      (node (ref "R9") (pin "1") (pinfunction "TOP_1") (pintype "passive"))
    )
    (net (code "69") (name "unconnected-(R10-TOP-Pad1)") (class "Default")
      (node (ref "R10") (pin "1") (pinfunction "TOP_1") (pintype "passive"))
    )
    (net (code "70") (name "unconnected-(R11-TOP-Pad1)") (class "Default")
      (node (ref "R11") (pin "1") (pinfunction "TOP_1") (pintype "passive"))
    )
    (net (code "71") (name "unconnected-(U2-GPIO4-Pad6)") (class "Default")
      (node (ref "U2") (pin "6") (pinfunction "GPIO4_6") (pintype "passive"))
    )
    (net (code "72") (name "unconnected-(U2-GPIO5-Pad7)") (class "Default")
      (node (ref "U2") (pin "7") (pinfunction "GPIO5_7") (pintype "passive"))
    )
    (net (code "73") (name "unconnected-(U2-GPIO6-Pad8)") (class "Default")
      (node (ref "U2") (pin "8") (pinfunction "GPIO6_8") (pintype "passive"))
    )
    (net (code "74") (name "unconnected-(U2-GPIO9-Pad12)") (class "Default")
      (node (ref "U2") (pin "12") (pinfunction "GPIO9_12") (pintype "passive"))
    )
    (net (code "75") (name "unconnected-(U2-GPIO10-Pad13)") (class "Default")
      (node (ref "U2") (pin "13") (pinfunction "GPIO10_13") (pintype "passive"))
    )
    (net (code "76") (name "unconnected-(U2-GPIO11-Pad14)") (class "Default")
      (node (ref "U2") (pin "14") (pinfunction "GPIO11_14") (pintype "passive"))
    )
    (net (code "77") (name "unconnected-(U2-GPIO12-Pad15)") (class "Default")
      (node (ref "U2") (pin "15") (pinfunction "GPIO12_15") (pintype "passive"))
    )
    (net (code "78") (name "unconnected-(U2-GPIO24-Pad36)") (class "Default")
      (node (ref "U2") (pin "36") (pinfunction "GPIO24_36") (pintype "passive+no_connect"))
    )
    (net (code "79") (name "unconnected-(U2-GPIO25-Pad37)") (class "Default")
      (node (ref "U2") (pin "37") (pinfunction "GPIO25_37") (pintype "passive+no_connect"))
    )
    (net (code "80") (name "unconnected-(U2-GPIO29{slash}ADC3-Pad41)") (class "Default")
      (node (ref "U2") (pin "41") (pinfunction "GPIO29/ADC3_41") (pintype "passive"))
    )
  )
)
